# Keg_Cop_-_Daisy_Chain_Molex.net
KiCad netlist of a schematic drawn in EAGLE
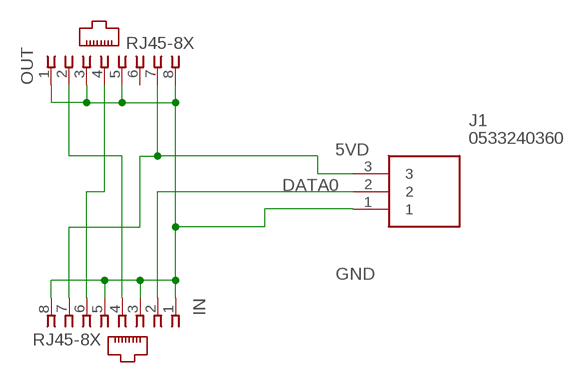
[diagram p0: schematic, sheet 1]

(export (version "E")
  (design (tool "Eeschema 10.0.6"))
  (components
    (comp (ref "IN")
      (value "RJ45-8X")
      (footprint "eagle-import:RJ45-NO-SHIELD")
      (libsource (lib "eagle-import") (part "RJ45-8X"))
    )
    (comp (ref "J1")
      (value "0533240360")
      (footprint "eagle-import:0533240360")
      (libsource (lib "eagle-import") (part "0533240360"))
    )
    (comp (ref "OUT")
      (value "RJ45-8X")
      (footprint "eagle-import:RJ45-NO-SHIELD")
      (libsource (lib "eagle-import") (part "RJ45-8X"))
    )
  )
  (nets
    (net (code "1") (name "/5VD") (class "Default")
      (node (ref "IN") (pin "7") (pinfunction "7_7") (pintype "passive"))
      (node (ref "J1") (pin "3") (pinfunction "3_3") (pintype "bidirectional"))
      (node (ref "OUT") (pin "7") (pinfunction "7_7") (pintype "passive"))
    )
    (net (code "2") (name "/DATA0") (class "Default")
      (node (ref "IN") (pin "2") (pinfunction "2_2") (pintype "passive"))
      (node (ref "J1") (pin "2") (pinfunction "2_2") (pintype "bidirectional"))
    )
    (net (code "3") (name "/GND") (class "Default")
      (node (ref "IN") (pin "1") (pinfunction "1_1") (pintype "passive"))
      (node (ref "IN") (pin "3") (pinfunction "3_3") (pintype "passive"))
      (node (ref "IN") (pin "5") (pinfunction "5_5") (pintype "passive"))
      (node (ref "IN") (pin "8") (pinfunction "8_8") (pintype "passive"))
      (node (ref "J1") (pin "1") (pinfunction "1_1") (pintype "bidirectional"))
      (node (ref "OUT") (pin "1") (pinfunction "1_1") (pintype "passive"))
      (node (ref "OUT") (pin "3") (pinfunction "3_3") (pintype "passive"))
      (node (ref "OUT") (pin "5") (pinfunction "5_5") (pintype "passive"))
      (node (ref "OUT") (pin "8") (pinfunction "8_8") (pintype "passive"))
    )
    (net (code "4") (name "Net-(IN-Pad4)") (class "Default")
      (node (ref "IN") (pin "4") (pinfunction "4_4") (pintype "passive"))
      (node (ref "OUT") (pin "2") (pinfunction "2_2") (pintype "passive"))
    )
    (net (code "5") (name "Net-(IN-Pad6)") (class "Default")
      (node (ref "IN") (pin "6") (pinfunction "6_6") (pintype "passive"))
      (node (ref "OUT") (pin "4") (pinfunction "4_4") (pintype "passive"))
    )
    (net (code "6") (name "unconnected-(OUT-Pad6)") (class "Default")
      (node (ref "OUT") (pin "6") (pinfunction "6_6") (pintype "passive"))
    )
  )
)
